# imu.net
KiCad netlist of a schematic drawn in EAGLE
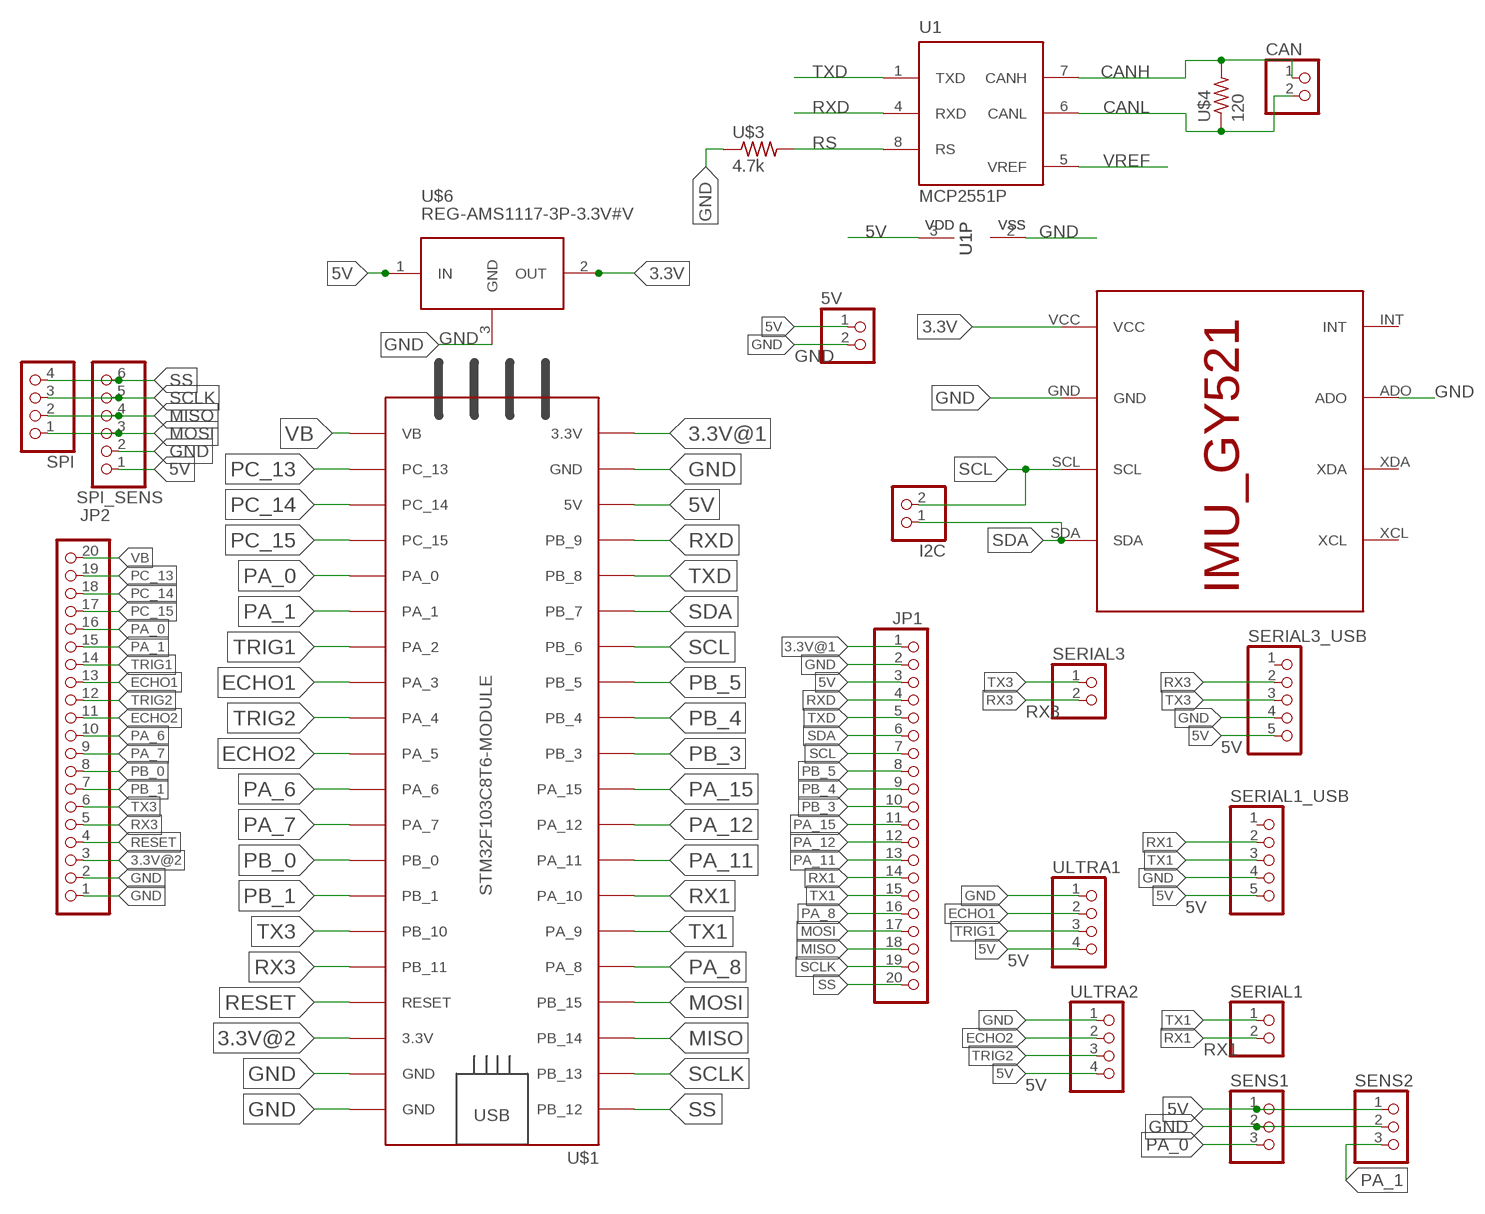
[diagram p0: schematic, sheet 1]

(export (version "E")
  (design (tool "Eeschema 10.0.6"))
  (components
    (comp (ref "5V")
      (value "PINHD-2_DATA")
      (footprint "eagle-import:1X02_DATA")
      (libsource (lib "eagle-import") (part "PINHD-2_DATA"))
    )
    (comp (ref "CAN")
      (value "PINHD-2_DATA")
      (footprint "eagle-import:1X02_DATA")
      (libsource (lib "eagle-import") (part "PINHD-2_DATA"))
    )
    (comp (ref "I2C")
      (value "PINHD-2_DATA")
      (footprint "eagle-import:1X02_DATA")
      (libsource (lib "eagle-import") (part "PINHD-2_DATA"))
    )
    (comp (ref "JP1")
      (value "PINHD-1X20")
      (footprint "eagle-import:1X20")
      (libsource (lib "eagle-import") (part "PINHD-1X20"))
    )
    (comp (ref "JP2")
      (value "PINHD-1X20")
      (footprint "eagle-import:1X20")
      (libsource (lib "eagle-import") (part "PINHD-1X20"))
    )
    (comp (ref "SENS1")
      (value "PINHD-3_DATA")
      (footprint "eagle-import:1X03_DATA")
      (libsource (lib "eagle-import") (part "PINHD-3_DATA"))
    )
    (comp (ref "SENS2")
      (value "PINHD-3_DATA")
      (footprint "eagle-import:1X03_DATA")
      (libsource (lib "eagle-import") (part "PINHD-3_DATA"))
    )
    (comp (ref "SERIAL1")
      (value "PINHD-2_DATA")
      (footprint "eagle-import:1X02_DATA")
      (libsource (lib "eagle-import") (part "PINHD-2_DATA"))
    )
    (comp (ref "SERIAL1_USB")
      (value "PINHD-5_DATA")
      (footprint "eagle-import:1X05_DATA")
      (libsource (lib "eagle-import") (part "PINHD-5_DATA"))
    )
    (comp (ref "SERIAL3")
      (value "PINHD-2_DATA")
      (footprint "eagle-import:1X02_DATA")
      (libsource (lib "eagle-import") (part "PINHD-2_DATA"))
    )
    (comp (ref "SERIAL3_USB")
      (value "PINHD-5_DATA")
      (footprint "eagle-import:1X05_DATA")
      (libsource (lib "eagle-import") (part "PINHD-5_DATA"))
    )
    (comp (ref "SPI")
      (value "PINHD-4_DATA")
      (footprint "eagle-import:1X04_DATA")
      (libsource (lib "eagle-import") (part "PINHD-4_DATA"))
    )
    (comp (ref "SPI_SENS")
      (value "PINHD-6_DATA")
      (footprint "eagle-import:1X06_DATA")
      (libsource (lib "eagle-import") (part "PINHD-6_DATA"))
    )
    (comp (ref "U$1")
      (value "STM32F103C8T6-MODULE")
      (footprint "eagle-import:STM32F103C8T6-MODULE")
      (libsource (lib "eagle-import") (part "STM32F103C8T6-MODULE"))
    )
    (comp (ref "U$2")
      (value "IMU_MPU6050")
      (footprint "eagle-import:IMU_GY521")
      (libsource (lib "eagle-import") (part "IMU_ROBOCON_GY521"))
    )
    (comp (ref "U$3")
      (value "4.7k")
      (footprint "eagle-import:0204_7")
      (libsource (lib "eagle-import") (part "RES-7"))
    )
    (comp (ref "U$4")
      (value "120")
      (footprint "eagle-import:0204_7")
      (libsource (lib "eagle-import") (part "RES-7"))
    )
    (comp (ref "U$6")
      (value "REG-AMS1117-3P-3.3V#V")
      (footprint "eagle-import:REG-AMS1117-3P#V")
      (libsource (lib "eagle-import") (part "REG-AMS1117-3P-#V3.3V"))
    )
    (comp (ref "U1")
      (value "MCP2551P")
      (footprint "eagle-import:DIL8")
      (libsource (lib "eagle-import") (part "MCP2551P"))
    )
    (comp (ref "ULTRA1")
      (value "PINHD-4_DATA")
      (footprint "eagle-import:1X04_DATA")
      (libsource (lib "eagle-import") (part "PINHD-4_DATA"))
    )
    (comp (ref "ULTRA2")
      (value "PINHD-4_DATA")
      (footprint "eagle-import:1X04_DATA")
      (libsource (lib "eagle-import") (part "PINHD-4_DATA"))
    )
  )
  (nets
    (net (code "1") (name "/CANH") (class "Default")
      (node (ref "CAN") (pin "1") (pinfunction "1_1") (pintype "passive"))
      (node (ref "U$4") (pin "2") (pinfunction "2_2") (pintype "passive"))
      (node (ref "U1") (pin "7") (pinfunction "CANH_7") (pintype "bidirectional"))
    )
    (net (code "2") (name "/CANL") (class "Default")
      (node (ref "CAN") (pin "2") (pinfunction "2_2") (pintype "passive"))
      (node (ref "U$4") (pin "1") (pinfunction "1_1") (pintype "passive"))
      (node (ref "U1") (pin "6") (pinfunction "CANL_6") (pintype "bidirectional"))
    )
    (net (code "3") (name "/RS") (class "Default")
      (node (ref "U$3") (pin "2") (pinfunction "2_2") (pintype "passive"))
      (node (ref "U1") (pin "8") (pinfunction "RS_8") (pintype "input"))
    )
    (net (code "4") (name "/VREF") (class "Default")
      (node (ref "U1") (pin "5") (pinfunction "VREF_5") (pintype "power_in"))
    )
    (net (code "5") (name "3.3V") (class "Default")
      (node (ref "U$2") (pin "VCC") (pinfunction "VCC_VCC") (pintype "bidirectional"))
      (node (ref "U$6") (pin "2") (pinfunction "OUT_2") (pintype "bidirectional"))
    )
    (net (code "6") (name "3.3V@1") (class "Default")
      (node (ref "JP1") (pin "1") (pinfunction "1_1") (pintype "passive"))
      (node (ref "U$1") (pin "3.3V_1") (pinfunction "3.3V_3.3V_1") (pintype "bidirectional"))
    )
    (net (code "7") (name "3.3V@2") (class "Default")
      (node (ref "JP2") (pin "3") (pinfunction "3_3") (pintype "passive"))
      (node (ref "U$1") (pin "3.3V_2") (pinfunction "3.3V_3.3V_2") (pintype "bidirectional"))
    )
    (net (code "8") (name "5V") (class "Default")
      (node (ref "5V") (pin "1") (pinfunction "1_1") (pintype "passive"))
      (node (ref "JP1") (pin "3") (pinfunction "3_3") (pintype "passive"))
      (node (ref "SENS1") (pin "1") (pinfunction "1_1") (pintype "passive"))
      (node (ref "SENS2") (pin "1") (pinfunction "1_1") (pintype "passive"))
      (node (ref "SERIAL1_USB") (pin "5") (pinfunction "5_5") (pintype "passive"))
      (node (ref "SERIAL3_USB") (pin "5") (pinfunction "5_5") (pintype "passive"))
      (node (ref "SPI_SENS") (pin "1") (pinfunction "1_1") (pintype "passive"))
      (node (ref "U$1") (pin "5V") (pinfunction "5V_5V") (pintype "bidirectional"))
      (node (ref "U$6") (pin "1") (pinfunction "IN_1") (pintype "bidirectional"))
      (node (ref "U1") (pin "3") (pinfunction "VDD_3") (pintype "power_in"))
      (node (ref "ULTRA1") (pin "4") (pinfunction "4_4") (pintype "passive"))
      (node (ref "ULTRA2") (pin "4") (pinfunction "4_4") (pintype "passive"))
    )
    (net (code "9") (name "ECHO1") (class "Default")
      (node (ref "JP2") (pin "13") (pinfunction "13_13") (pintype "passive"))
      (node (ref "U$1") (pin "PA_3") (pinfunction "PA_3_PA_3") (pintype "bidirectional"))
      (node (ref "ULTRA1") (pin "2") (pinfunction "2_2") (pintype "passive"))
    )
    (net (code "10") (name "ECHO2") (class "Default")
      (node (ref "JP2") (pin "11") (pinfunction "11_11") (pintype "passive"))
      (node (ref "U$1") (pin "PA_5") (pinfunction "PA_5_PA_5") (pintype "bidirectional"))
      (node (ref "ULTRA2") (pin "2") (pinfunction "2_2") (pintype "passive"))
    )
    (net (code "11") (name "GND") (class "Default")
      (node (ref "5V") (pin "2") (pinfunction "2_2") (pintype "passive"))
      (node (ref "JP1") (pin "2") (pinfunction "2_2") (pintype "passive"))
      (node (ref "JP2") (pin "1") (pinfunction "1_1") (pintype "passive"))
      (node (ref "JP2") (pin "2") (pinfunction "2_2") (pintype "passive"))
      (node (ref "SENS1") (pin "2") (pinfunction "2_2") (pintype "passive"))
      (node (ref "SENS2") (pin "2") (pinfunction "2_2") (pintype "passive"))
      (node (ref "SERIAL1_USB") (pin "4") (pinfunction "4_4") (pintype "passive"))
      (node (ref "SERIAL3_USB") (pin "4") (pinfunction "4_4") (pintype "passive"))
      (node (ref "SPI_SENS") (pin "2") (pinfunction "2_2") (pintype "passive"))
      (node (ref "U$1") (pin "GND_1") (pinfunction "GND_GND_1") (pintype "bidirectional"))
      (node (ref "U$1") (pin "GND_2") (pinfunction "GND_GND_2") (pintype "bidirectional"))
      (node (ref "U$1") (pin "GND_3") (pinfunction "GND_GND_3") (pintype "power_in"))
      (node (ref "U$2") (pin "ADO") (pinfunction "ADO_ADO") (pintype "bidirectional"))
      (node (ref "U$2") (pin "GND") (pinfunction "GND_GND") (pintype "bidirectional"))
      (node (ref "U$3") (pin "1") (pinfunction "1_1") (pintype "passive"))
      (node (ref "U$6") (pin "3") (pinfunction "GND_3") (pintype "bidirectional"))
      (node (ref "U1") (pin "2") (pinfunction "VSS_2") (pintype "power_in"))
      (node (ref "ULTRA1") (pin "1") (pinfunction "1_1") (pintype "passive"))
      (node (ref "ULTRA2") (pin "1") (pinfunction "1_1") (pintype "passive"))
    )
    (net (code "12") (name "MISO") (class "Default")
      (node (ref "JP1") (pin "18") (pinfunction "18_18") (pintype "passive"))
      (node (ref "SPI") (pin "2") (pinfunction "2_2") (pintype "passive"))
      (node (ref "SPI_SENS") (pin "4") (pinfunction "4_4") (pintype "passive"))
      (node (ref "U$1") (pin "PB_14") (pinfunction "PB_14_PB_14") (pintype "bidirectional"))
    )
    (net (code "13") (name "MOSI") (class "Default")
      (node (ref "JP1") (pin "17") (pinfunction "17_17") (pintype "passive"))
      (node (ref "SPI") (pin "1") (pinfunction "1_1") (pintype "passive"))
      (node (ref "SPI_SENS") (pin "3") (pinfunction "3_3") (pintype "passive"))
      (node (ref "U$1") (pin "PB_15") (pinfunction "PB_15_PB_15") (pintype "bidirectional"))
    )
    (net (code "14") (name "PA_0") (class "Default")
      (node (ref "JP2") (pin "16") (pinfunction "16_16") (pintype "passive"))
      (node (ref "SENS1") (pin "3") (pinfunction "3_3") (pintype "passive"))
      (node (ref "U$1") (pin "PA_0") (pinfunction "PA_0_PA_0") (pintype "bidirectional"))
    )
    (net (code "15") (name "PA_1") (class "Default")
      (node (ref "JP2") (pin "15") (pinfunction "15_15") (pintype "passive"))
      (node (ref "SENS2") (pin "3") (pinfunction "3_3") (pintype "passive"))
      (node (ref "U$1") (pin "PA_1") (pinfunction "PA_1_PA_1") (pintype "bidirectional"))
    )
    (net (code "16") (name "PA_6") (class "Default")
      (node (ref "JP2") (pin "10") (pinfunction "10_10") (pintype "passive"))
      (node (ref "U$1") (pin "PA_6") (pinfunction "PA_6_PA_6") (pintype "bidirectional"))
    )
    (net (code "17") (name "PA_7") (class "Default")
      (node (ref "JP2") (pin "9") (pinfunction "9_9") (pintype "passive"))
      (node (ref "U$1") (pin "PA_7") (pinfunction "PA_7_PA_7") (pintype "bidirectional"))
    )
    (net (code "18") (name "PA_8") (class "Default")
      (node (ref "JP1") (pin "16") (pinfunction "16_16") (pintype "passive"))
      (node (ref "U$1") (pin "PA_8") (pinfunction "PA_8_PA_8") (pintype "bidirectional"))
    )
    (net (code "19") (name "PA_11") (class "Default")
      (node (ref "JP1") (pin "13") (pinfunction "13_13") (pintype "passive"))
      (node (ref "U$1") (pin "PA_11") (pinfunction "PA_11_PA_11") (pintype "bidirectional"))
    )
    (net (code "20") (name "PA_12") (class "Default")
      (node (ref "JP1") (pin "12") (pinfunction "12_12") (pintype "passive"))
      (node (ref "U$1") (pin "PA_12") (pinfunction "PA_12_PA_12") (pintype "bidirectional"))
    )
    (net (code "21") (name "PA_15") (class "Default")
      (node (ref "JP1") (pin "11") (pinfunction "11_11") (pintype "passive"))
      (node (ref "U$1") (pin "PA_15") (pinfunction "PA_15_PA_15") (pintype "bidirectional"))
    )
    (net (code "22") (name "PB_0") (class "Default")
      (node (ref "JP2") (pin "8") (pinfunction "8_8") (pintype "passive"))
      (node (ref "U$1") (pin "PB_0") (pinfunction "PB_0_PB_0") (pintype "bidirectional"))
    )
    (net (code "23") (name "PB_1") (class "Default")
      (node (ref "JP2") (pin "7") (pinfunction "7_7") (pintype "passive"))
      (node (ref "U$1") (pin "PB_1") (pinfunction "PB_1_PB_1") (pintype "bidirectional"))
    )
    (net (code "24") (name "PB_3") (class "Default")
      (node (ref "JP1") (pin "10") (pinfunction "10_10") (pintype "passive"))
      (node (ref "U$1") (pin "PB_3") (pinfunction "PB_3_PB_3") (pintype "bidirectional"))
    )
    (net (code "25") (name "PB_4") (class "Default")
      (node (ref "JP1") (pin "9") (pinfunction "9_9") (pintype "passive"))
      (node (ref "U$1") (pin "PB_4") (pinfunction "PB_4_PB_4") (pintype "bidirectional"))
    )
    (net (code "26") (name "PB_5") (class "Default")
      (node (ref "JP1") (pin "8") (pinfunction "8_8") (pintype "passive"))
      (node (ref "U$1") (pin "PB_5") (pinfunction "PB_5_PB_5") (pintype "bidirectional"))
    )
    (net (code "27") (name "PC_13") (class "Default")
      (node (ref "JP2") (pin "19") (pinfunction "19_19") (pintype "passive"))
      (node (ref "U$1") (pin "PC_13") (pinfunction "PC_13_PC_13") (pintype "bidirectional"))
    )
    (net (code "28") (name "PC_14") (class "Default")
      (node (ref "JP2") (pin "18") (pinfunction "18_18") (pintype "passive"))
      (node (ref "U$1") (pin "PC_14") (pinfunction "PC_14_PC_14") (pintype "bidirectional"))
    )
    (net (code "29") (name "PC_15") (class "Default")
      (node (ref "JP2") (pin "17") (pinfunction "17_17") (pintype "passive"))
      (node (ref "U$1") (pin "PC_15") (pinfunction "PC_15_PC_15") (pintype "bidirectional"))
    )
    (net (code "30") (name "RESET") (class "Default")
      (node (ref "JP2") (pin "4") (pinfunction "4_4") (pintype "passive"))
      (node (ref "U$1") (pin "RESET") (pinfunction "RESET_RESET") (pintype "bidirectional"))
    )
    (net (code "31") (name "RX1") (class "Default")
      (node (ref "JP1") (pin "14") (pinfunction "14_14") (pintype "passive"))
      (node (ref "SERIAL1") (pin "2") (pinfunction "2_2") (pintype "passive"))
      (node (ref "SERIAL1_USB") (pin "2") (pinfunction "2_2") (pintype "passive"))
      (node (ref "U$1") (pin "PA_10") (pinfunction "PA_10_PA_10") (pintype "bidirectional"))
    )
    (net (code "32") (name "RX3") (class "Default")
      (node (ref "JP2") (pin "5") (pinfunction "5_5") (pintype "passive"))
      (node (ref "SERIAL3") (pin "2") (pinfunction "2_2") (pintype "passive"))
      (node (ref "SERIAL3_USB") (pin "2") (pinfunction "2_2") (pintype "passive"))
      (node (ref "U$1") (pin "PB_11") (pinfunction "PB_11_PB_11") (pintype "bidirectional"))
    )
    (net (code "33") (name "RXD") (class "Default")
      (node (ref "JP1") (pin "4") (pinfunction "4_4") (pintype "passive"))
      (node (ref "U$1") (pin "PB_9") (pinfunction "PB_9_PB_9") (pintype "bidirectional"))
      (node (ref "U1") (pin "4") (pinfunction "RXD_4") (pintype "output"))
    )
    (net (code "34") (name "SCL") (class "Default")
      (node (ref "I2C") (pin "2") (pinfunction "2_2") (pintype "passive"))
      (node (ref "JP1") (pin "7") (pinfunction "7_7") (pintype "passive"))
      (node (ref "U$1") (pin "PB_6") (pinfunction "PB_6_PB_6") (pintype "bidirectional"))
      (node (ref "U$2") (pin "SCL") (pinfunction "SCL_SCL") (pintype "bidirectional"))
    )
    (net (code "35") (name "SCLK") (class "Default")
      (node (ref "JP1") (pin "19") (pinfunction "19_19") (pintype "passive"))
      (node (ref "SPI") (pin "3") (pinfunction "3_3") (pintype "passive"))
      (node (ref "SPI_SENS") (pin "5") (pinfunction "5_5") (pintype "passive"))
      (node (ref "U$1") (pin "PB_13") (pinfunction "PB_13_PB_13") (pintype "bidirectional"))
    )
    (net (code "36") (name "SDA") (class "Default")
      (node (ref "I2C") (pin "1") (pinfunction "1_1") (pintype "passive"))
      (node (ref "JP1") (pin "6") (pinfunction "6_6") (pintype "passive"))
      (node (ref "U$1") (pin "PB_7") (pinfunction "PB_7_PB_7") (pintype "bidirectional"))
      (node (ref "U$2") (pin "SDA") (pinfunction "SDA_SDA") (pintype "bidirectional"))
    )
    (net (code "37") (name "SS") (class "Default")
      (node (ref "JP1") (pin "20") (pinfunction "20_20") (pintype "passive"))
      (node (ref "SPI") (pin "4") (pinfunction "4_4") (pintype "passive"))
      (node (ref "SPI_SENS") (pin "6") (pinfunction "6_6") (pintype "passive"))
      (node (ref "U$1") (pin "PB_12") (pinfunction "PB_12_PB_12") (pintype "bidirectional"))
    )
    (net (code "38") (name "TRIG1") (class "Default")
      (node (ref "JP2") (pin "14") (pinfunction "14_14") (pintype "passive"))
      (node (ref "U$1") (pin "PA_2") (pinfunction "PA_2_PA_2") (pintype "bidirectional"))
      (node (ref "ULTRA1") (pin "3") (pinfunction "3_3") (pintype "passive"))
    )
    (net (code "39") (name "TRIG2") (class "Default")
      (node (ref "JP2") (pin "12") (pinfunction "12_12") (pintype "passive"))
      (node (ref "U$1") (pin "PA_4") (pinfunction "PA_4_PA_4") (pintype "bidirectional"))
      (node (ref "ULTRA2") (pin "3") (pinfunction "3_3") (pintype "passive"))
    )
    (net (code "40") (name "TX1") (class "Default")
      (node (ref "JP1") (pin "15") (pinfunction "15_15") (pintype "passive"))
      (node (ref "SERIAL1") (pin "1") (pinfunction "1_1") (pintype "passive"))
      (node (ref "SERIAL1_USB") (pin "3") (pinfunction "3_3") (pintype "passive"))
      (node (ref "U$1") (pin "PA_9") (pinfunction "PA_9_PA_9") (pintype "bidirectional"))
    )
    (net (code "41") (name "TX3") (class "Default")
      (node (ref "JP2") (pin "6") (pinfunction "6_6") (pintype "passive"))
      (node (ref "SERIAL3") (pin "1") (pinfunction "1_1") (pintype "passive"))
      (node (ref "SERIAL3_USB") (pin "3") (pinfunction "3_3") (pintype "passive"))
      (node (ref "U$1") (pin "PB_10") (pinfunction "PB_10_PB_10") (pintype "bidirectional"))
    )
    (net (code "42") (name "TXD") (class "Default")
      (node (ref "JP1") (pin "5") (pinfunction "5_5") (pintype "passive"))
      (node (ref "U$1") (pin "PB_8") (pinfunction "PB_8_PB_8") (pintype "bidirectional"))
      (node (ref "U1") (pin "1") (pinfunction "TXD_1") (pintype "input"))
    )
    (net (code "43") (name "VB") (class "Default")
      (node (ref "JP2") (pin "20") (pinfunction "20_20") (pintype "passive"))
      (node (ref "U$1") (pin "VB") (pinfunction "VB_VB") (pintype "bidirectional"))
    )
    (net (code "44") (name "unconnected-(SERIAL1_USB-Pad1)") (class "Default")
      (node (ref "SERIAL1_USB") (pin "1") (pinfunction "1_1") (pintype "passive"))
    )
    (net (code "45") (name "unconnected-(SERIAL3_USB-Pad1)") (class "Default")
      (node (ref "SERIAL3_USB") (pin "1") (pinfunction "1_1") (pintype "passive"))
    )
    (net (code "46") (name "unconnected-(U$2-PadINT)") (class "Default")
      (node (ref "U$2") (pin "INT") (pinfunction "INT_INT") (pintype "bidirectional"))
    )
    (net (code "47") (name "unconnected-(U$2-PadXCL)") (class "Default")
      (node (ref "U$2") (pin "XCL") (pinfunction "XCL_XCL") (pintype "bidirectional"))
    )
    (net (code "48") (name "unconnected-(U$2-PadXDA)") (class "Default")
      (node (ref "U$2") (pin "XDA") (pinfunction "XDA_XDA") (pintype "bidirectional"))
    )
  )
)
